# level_shifter_v1_0.net
KiCad netlist of a schematic drawn in EAGLE
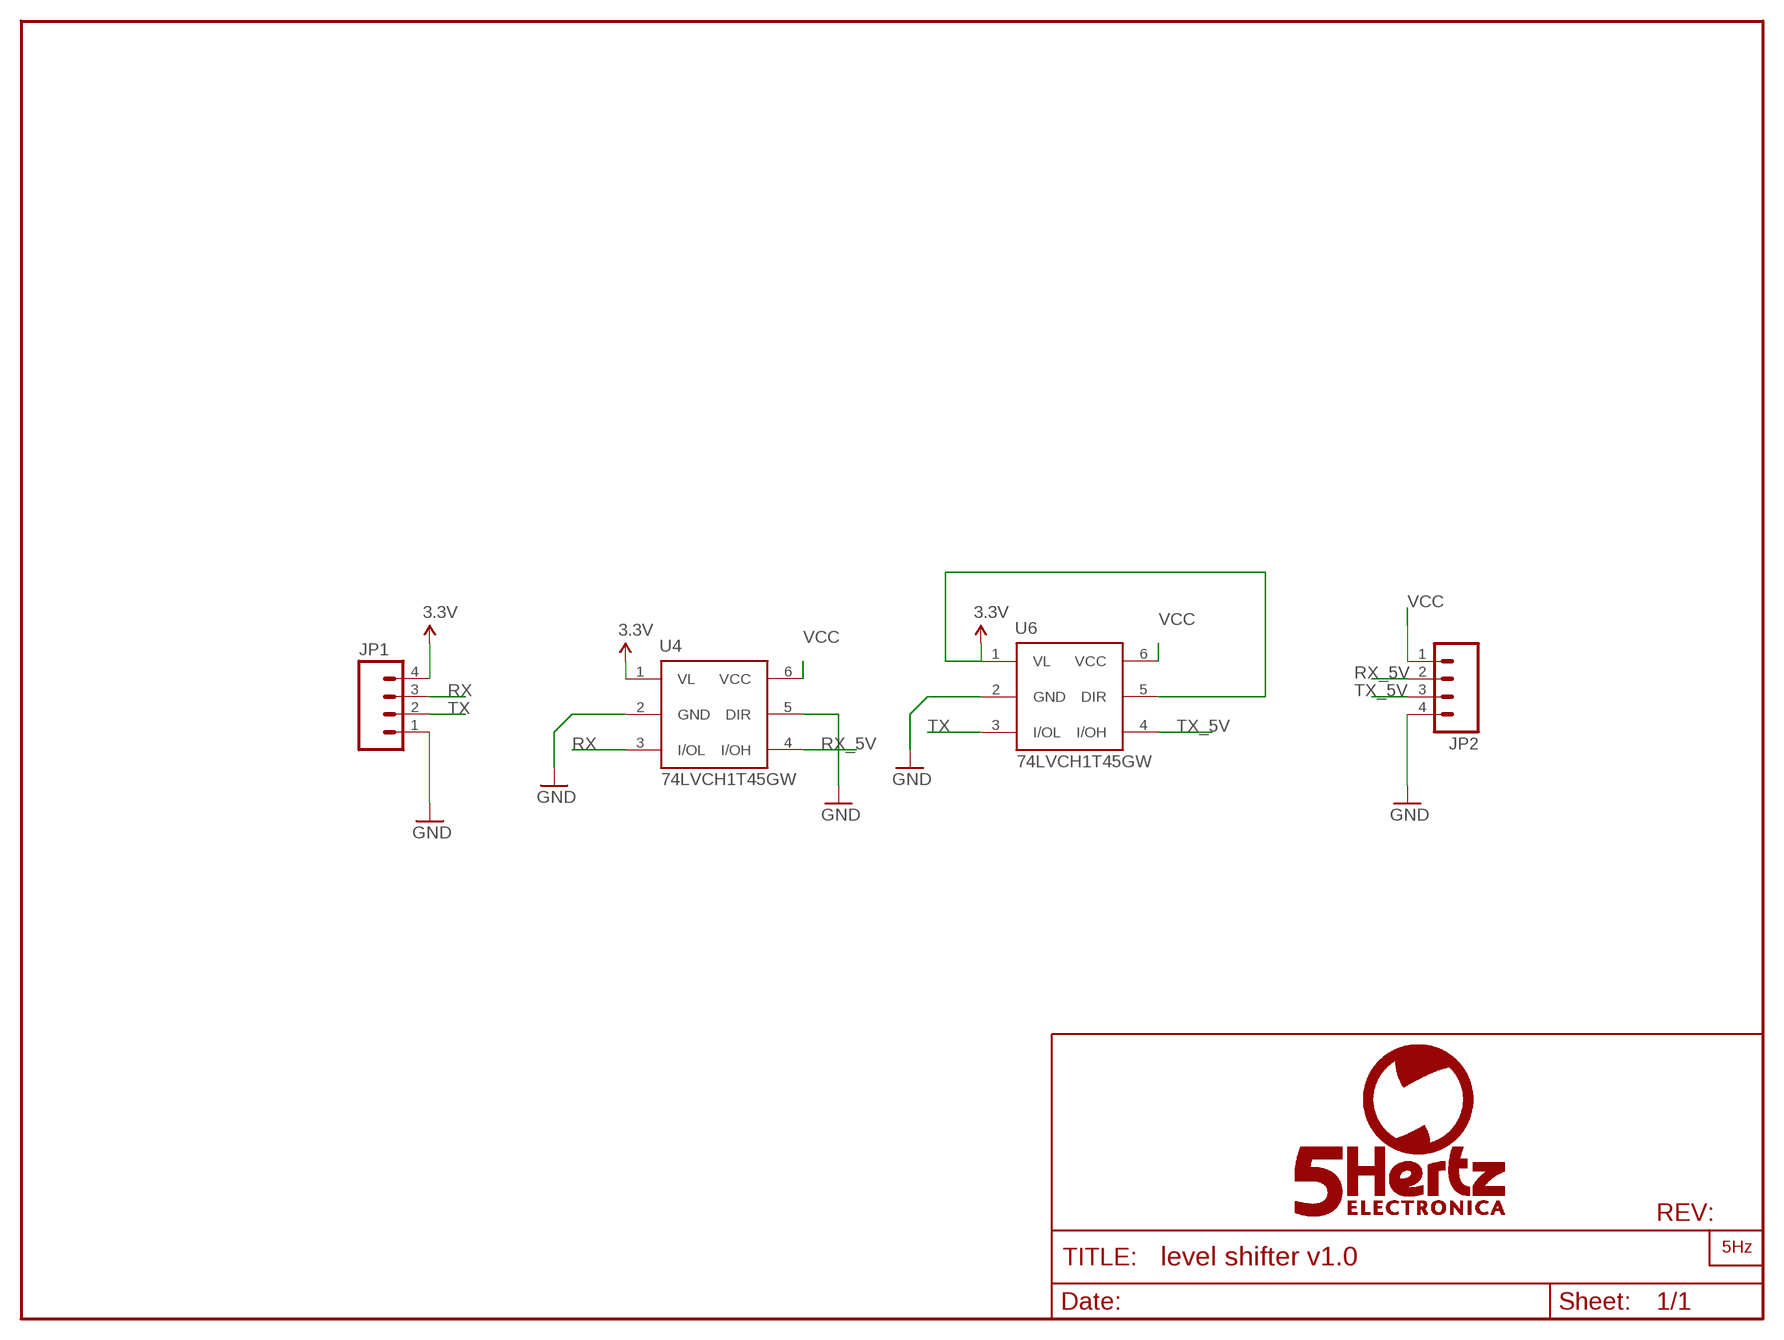
[diagram p0: schematic, sheet 1]

(export (version "E")
  (design (tool "Eeschema 10.0.6"))
  (components
    (comp (ref "JP1")
      (value "M04PTH")
      (footprint "eagle-import:1X04")
      (libsource (lib "eagle-import") (part "M04PTH"))
    )
    (comp (ref "JP2")
      (value "M04PTH")
      (footprint "eagle-import:1X04")
      (libsource (lib "eagle-import") (part "M04PTH"))
    )
    (comp (ref "U$1")
      (value "LOGO_COPPER5MM")
      (footprint "eagle-import:LOGO_COP_5MM")
      (libsource (lib "eagle-import") (part "LOGO_COPPER5MM"))
    )
    (comp (ref "U4")
      (value "74LVCH1T45GW")
      (footprint "eagle-import:SOT-363")
      (libsource (lib "eagle-import") (part "74LVCH1T45GW"))
    )
    (comp (ref "U6")
      (value "74LVCH1T45GW")
      (footprint "eagle-import:SOT-363")
      (libsource (lib "eagle-import") (part "74LVCH1T45GW"))
    )
  )
  (nets
    (net (code "1") (name "/RX") (class "Default")
      (node (ref "JP1") (pin "3") (pinfunction "3_3") (pintype "passive"))
      (node (ref "U4") (pin "3") (pinfunction "I/OL_3") (pintype "bidirectional"))
    )
    (net (code "2") (name "/RX_5V") (class "Default")
      (node (ref "JP2") (pin "2") (pinfunction "2_2") (pintype "passive"))
      (node (ref "U4") (pin "4") (pinfunction "I/OH_4") (pintype "bidirectional"))
    )
    (net (code "3") (name "/TX") (class "Default")
      (node (ref "JP1") (pin "2") (pinfunction "2_2") (pintype "passive"))
      (node (ref "U6") (pin "3") (pinfunction "I/OL_3") (pintype "bidirectional"))
    )
    (net (code "4") (name "/TX_5V") (class "Default")
      (node (ref "JP2") (pin "3") (pinfunction "3_3") (pintype "passive"))
      (node (ref "U6") (pin "4") (pinfunction "I/OH_4") (pintype "bidirectional"))
    )
    (net (code "5") (name "/VCC") (class "Default")
      (node (ref "JP2") (pin "1") (pinfunction "1_1") (pintype "passive"))
      (node (ref "U4") (pin "6") (pinfunction "VCC_6") (pintype "bidirectional"))
      (node (ref "U6") (pin "6") (pinfunction "VCC_6") (pintype "bidirectional"))
    )
    (net (code "6") (name "3.3V") (class "Default")
      (node (ref "JP1") (pin "4") (pinfunction "4_4") (pintype "passive"))
      (node (ref "U4") (pin "1") (pinfunction "VL_1") (pintype "bidirectional"))
      (node (ref "U6") (pin "1") (pinfunction "VL_1") (pintype "bidirectional"))
      (node (ref "U6") (pin "5") (pinfunction "DIR_5") (pintype "bidirectional"))
    )
    (net (code "7") (name "GND") (class "Default")
      (node (ref "JP1") (pin "1") (pinfunction "1_1") (pintype "passive"))
      (node (ref "JP2") (pin "4") (pinfunction "4_4") (pintype "passive"))
      (node (ref "U4") (pin "2") (pinfunction "GND_2") (pintype "bidirectional"))
      (node (ref "U4") (pin "5") (pinfunction "DIR_5") (pintype "bidirectional"))
      (node (ref "U6") (pin "2") (pinfunction "GND_2") (pintype "bidirectional"))
    )
  )
)
